# Irrigatron.net
KiCad netlist of a schematic drawn in EasyEDA
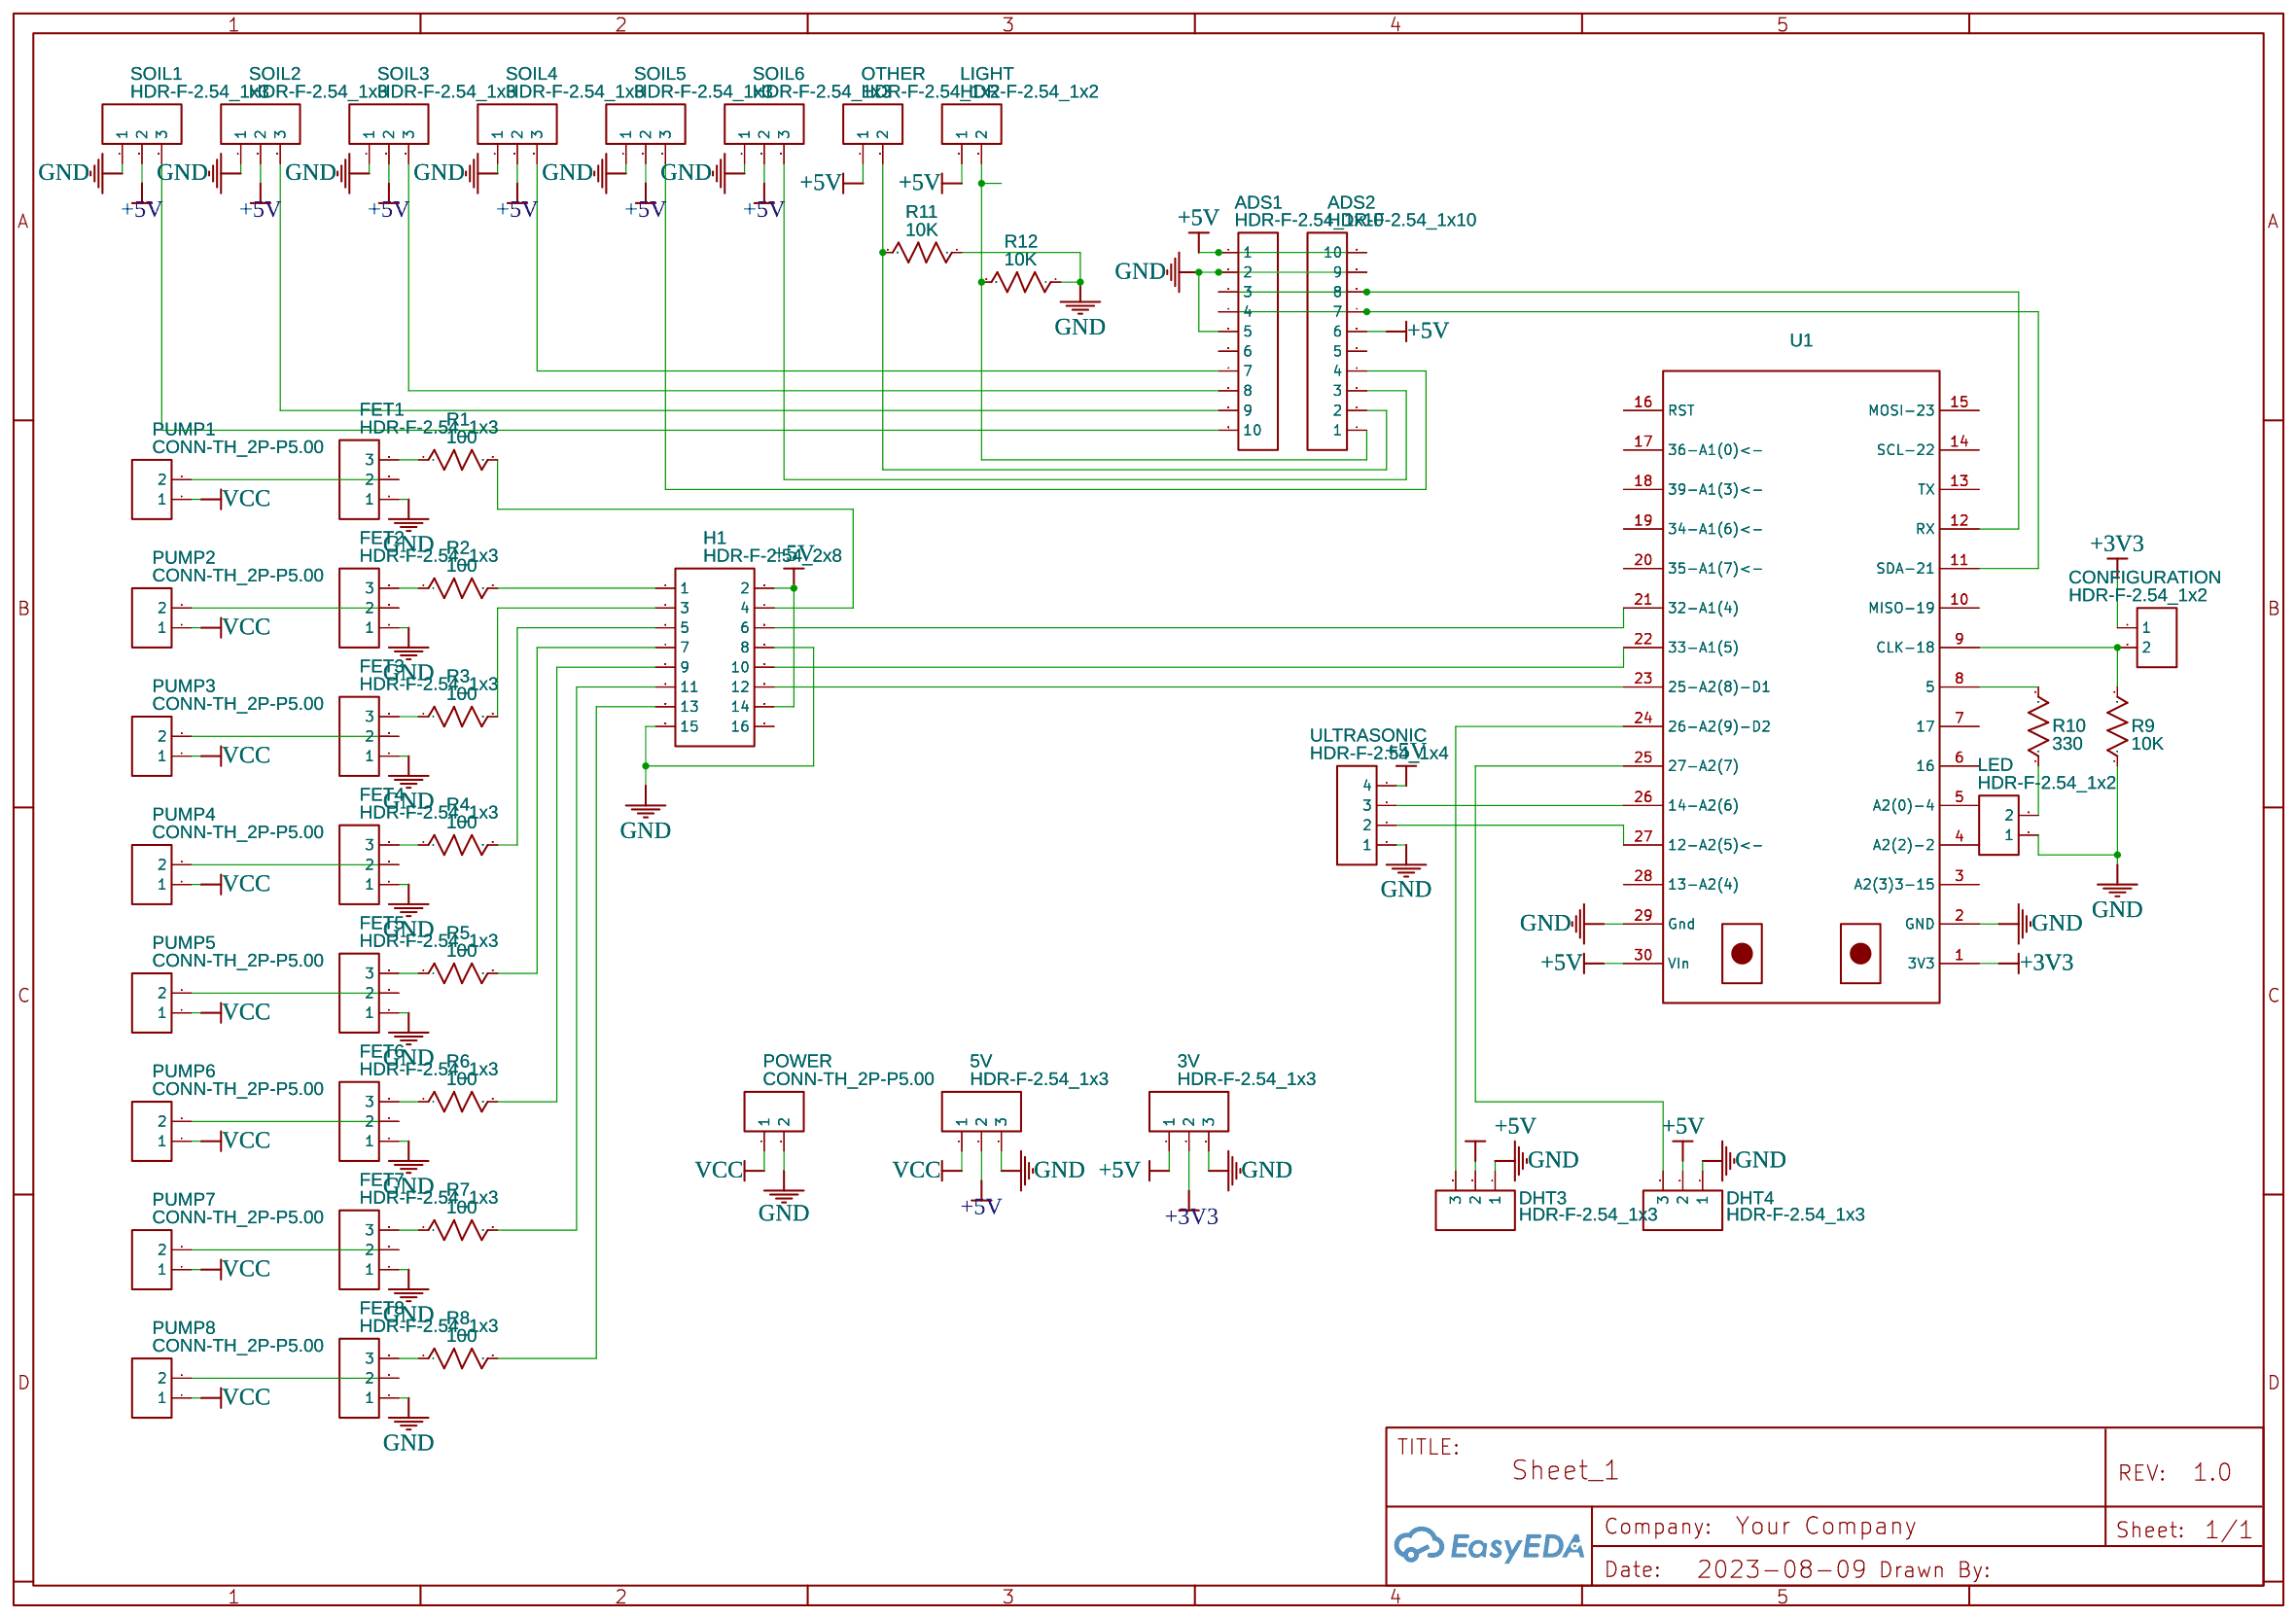
[diagram p0: schematic sheet]

(export (version "E")
  (design (tool "Eeschema 10.0.6"))
  (components
    (comp (ref "3V") (value "HDR-F-2.54_1x3") (libsource (lib "") (part "HDR-F-2.54_1x3_4")))
    (comp (ref "5V") (value "HDR-F-2.54_1x3") (libsource (lib "") (part "HDR-F-2.54_1x3_2")))
    (comp (ref "ADS1") (value "HDR-F-2.54_1x10") (libsource (lib "") (part "HDR-F-2.54_1x10_1")))
    (comp (ref "ADS2") (value "HDR-F-2.54_1x10") (libsource (lib "") (part "HDR-F-2.54_1x10")))
    (comp (ref "CONFIGURATION") (value "HDR-F-2.54_1x2") (libsource (lib "") (part "HDR-F-2.54_1x2_3")))
    (comp (ref "DHT3") (value "HDR-F-2.54_1x3") (libsource (lib "") (part "HDR-F-2.54_1x3_3")))
    (comp (ref "DHT4") (value "HDR-F-2.54_1x3") (libsource (lib "") (part "HDR-F-2.54_1x3_3")))
    (comp (ref "FET1") (value "HDR-F-2.54_1x3") (libsource (lib "") (part "HDR-F-2.54_1x3")))
    (comp (ref "FET2") (value "HDR-F-2.54_1x3") (libsource (lib "") (part "HDR-F-2.54_1x3")))
    (comp (ref "FET3") (value "HDR-F-2.54_1x3") (libsource (lib "") (part "HDR-F-2.54_1x3")))
    (comp (ref "FET4") (value "HDR-F-2.54_1x3") (libsource (lib "") (part "HDR-F-2.54_1x3")))
    (comp (ref "FET5") (value "HDR-F-2.54_1x3") (libsource (lib "") (part "HDR-F-2.54_1x3")))
    (comp (ref "FET6") (value "HDR-F-2.54_1x3") (libsource (lib "") (part "HDR-F-2.54_1x3")))
    (comp (ref "FET7") (value "HDR-F-2.54_1x3") (libsource (lib "") (part "HDR-F-2.54_1x3")))
    (comp (ref "FET8") (value "HDR-F-2.54_1x3") (libsource (lib "") (part "HDR-F-2.54_1x3")))
    (comp (ref "H1") (value "HDR-F-2.54_2x8") (libsource (lib "") (part "HDR-F-2.54_2x8")))
    (comp (ref "LED") (value "HDR-F-2.54_1x2") (libsource (lib "") (part "HDR-F-2.54_1x2")))
    (comp (ref "LIGHT") (value "HDR-F-2.54_1x2") (libsource (lib "") (part "HDR-F-2.54_1x2_2")))
    (comp (ref "OTHER") (value "HDR-F-2.54_1x2") (libsource (lib "") (part "HDR-F-2.54_1x2_1")))
    (comp (ref "POWER") (value "CONN-TH_2P-P5.00") (libsource (lib "") (part "CONN-TH_2P-P5.00")))
    (comp (ref "PUMP1") (value "CONN-TH_2P-P5.00") (libsource (lib "") (part "CONN-TH_2P-P5.00_1")))
    (comp (ref "PUMP2") (value "CONN-TH_2P-P5.00") (libsource (lib "") (part "CONN-TH_2P-P5.00_1")))
    (comp (ref "PUMP3") (value "CONN-TH_2P-P5.00") (libsource (lib "") (part "CONN-TH_2P-P5.00_1")))
    (comp (ref "PUMP4") (value "CONN-TH_2P-P5.00") (libsource (lib "") (part "CONN-TH_2P-P5.00_1")))
    (comp (ref "PUMP5") (value "CONN-TH_2P-P5.00") (libsource (lib "") (part "CONN-TH_2P-P5.00_1")))
    (comp (ref "PUMP6") (value "CONN-TH_2P-P5.00") (libsource (lib "") (part "CONN-TH_2P-P5.00_1")))
    (comp (ref "PUMP7") (value "CONN-TH_2P-P5.00") (libsource (lib "") (part "CONN-TH_2P-P5.00_1")))
    (comp (ref "PUMP8") (value "CONN-TH_2P-P5.00") (libsource (lib "") (part "CONN-TH_2P-P5.00_1")))
    (comp (ref "R1") (value "100") (libsource (lib "") (part "R_0603_US")))
    (comp (ref "R2") (value "100") (libsource (lib "") (part "R_0603_US")))
    (comp (ref "R3") (value "100") (libsource (lib "") (part "R_0603_US")))
    (comp (ref "R4") (value "100") (libsource (lib "") (part "R_0603_US")))
    (comp (ref "R5") (value "100") (libsource (lib "") (part "R_0603_US")))
    (comp (ref "R6") (value "100") (libsource (lib "") (part "R_0603_US")))
    (comp (ref "R7") (value "100") (libsource (lib "") (part "R_0603_US")))
    (comp (ref "R8") (value "100") (libsource (lib "") (part "R_0603_US")))
    (comp (ref "R9") (value "10K") (libsource (lib "") (part "R_0603_US_2")))
    (comp (ref "R10") (value "330") (libsource (lib "") (part "R_0603_US_2")))
    (comp (ref "R11") (value "10K") (libsource (lib "") (part "R_0603_US_1")))
    (comp (ref "R12") (value "10K") (libsource (lib "") (part "R_0603_US_1")))
    (comp (ref "SOIL1") (value "HDR-F-2.54_1x3") (libsource (lib "") (part "HDR-F-2.54_1x3_1")))
    (comp (ref "SOIL2") (value "HDR-F-2.54_1x3") (libsource (lib "") (part "HDR-F-2.54_1x3_1")))
    (comp (ref "SOIL3") (value "HDR-F-2.54_1x3") (libsource (lib "") (part "HDR-F-2.54_1x3_1")))
    (comp (ref "SOIL4") (value "HDR-F-2.54_1x3") (libsource (lib "") (part "HDR-F-2.54_1x3_1")))
    (comp (ref "SOIL5") (value "HDR-F-2.54_1x3") (libsource (lib "") (part "HDR-F-2.54_1x3_1")))
    (comp (ref "SOIL6") (value "HDR-F-2.54_1x3") (libsource (lib "") (part "HDR-F-2.54_1x3_1")))
    (comp (ref "U1") (value "NO") (libsource (lib "") (part "DOIT ESP32 DEVKIT V1 (30pins)")))
    (comp (ref "ULTRASONIC") (value "HDR-F-2.54_1x4") (libsource (lib "") (part "HDR-F-2.54_1x4")))
  )
  (nets
    (net (code "1") (name "+3V3") (class "Default")
      (node (ref "3V") (pin "2") (pinfunction "2_2") (pintype "input"))
      (node (ref "CONFIGURATION") (pin "1") (pinfunction "1_1") (pintype "input"))
      (node (ref "U1") (pin "1") (pinfunction "3V3_1") (pintype "unspecified"))
    )
    (net (code "2") (name "+5V") (class "Default")
      (node (ref "3V") (pin "1") (pinfunction "1_1") (pintype "input"))
      (node (ref "5V") (pin "2") (pinfunction "2_2") (pintype "input"))
      (node (ref "ADS1") (pin "1") (pinfunction "1_1") (pintype "unspecified"))
      (node (ref "ADS2") (pin "10") (pinfunction "10_10") (pintype "unspecified"))
      (node (ref "ADS2") (pin "6") (pinfunction "6_6") (pintype "unspecified"))
      (node (ref "DHT3") (pin "2") (pinfunction "2_2") (pintype "input"))
      (node (ref "DHT4") (pin "2") (pinfunction "2_2") (pintype "input"))
      (node (ref "H1") (pin "14") (pinfunction "14_14") (pintype "input"))
      (node (ref "H1") (pin "2") (pinfunction "2_2") (pintype "input"))
      (node (ref "LIGHT") (pin "1") (pinfunction "1_1") (pintype "input"))
      (node (ref "OTHER") (pin "1") (pinfunction "1_1") (pintype "input"))
      (node (ref "SOIL1") (pin "2") (pinfunction "2_2") (pintype "input"))
      (node (ref "SOIL2") (pin "2") (pinfunction "2_2") (pintype "input"))
      (node (ref "SOIL3") (pin "2") (pinfunction "2_2") (pintype "input"))
      (node (ref "SOIL4") (pin "2") (pinfunction "2_2") (pintype "input"))
      (node (ref "SOIL5") (pin "2") (pinfunction "2_2") (pintype "input"))
      (node (ref "SOIL6") (pin "2") (pinfunction "2_2") (pintype "input"))
      (node (ref "U1") (pin "30") (pinfunction "VIn_30") (pintype "unspecified"))
      (node (ref "ULTRASONIC") (pin "4") (pinfunction "4_4") (pintype "unspecified"))
    )
    (net (code "3") (name "GND") (class "Default")
      (node (ref "3V") (pin "3") (pinfunction "3_3") (pintype "input"))
      (node (ref "5V") (pin "3") (pinfunction "3_3") (pintype "input"))
      (node (ref "ADS1") (pin "2") (pinfunction "2_2") (pintype "unspecified"))
      (node (ref "ADS1") (pin "5") (pinfunction "5_5") (pintype "unspecified"))
      (node (ref "ADS2") (pin "9") (pinfunction "9_9") (pintype "unspecified"))
      (node (ref "DHT3") (pin "1") (pinfunction "1_1") (pintype "input"))
      (node (ref "DHT4") (pin "1") (pinfunction "1_1") (pintype "input"))
      (node (ref "FET1") (pin "1") (pinfunction "1_1") (pintype "input"))
      (node (ref "FET2") (pin "1") (pinfunction "1_1") (pintype "input"))
      (node (ref "FET3") (pin "1") (pinfunction "1_1") (pintype "input"))
      (node (ref "FET4") (pin "1") (pinfunction "1_1") (pintype "input"))
      (node (ref "FET5") (pin "1") (pinfunction "1_1") (pintype "input"))
      (node (ref "FET6") (pin "1") (pinfunction "1_1") (pintype "input"))
      (node (ref "FET7") (pin "1") (pinfunction "1_1") (pintype "input"))
      (node (ref "FET8") (pin "1") (pinfunction "1_1") (pintype "input"))
      (node (ref "H1") (pin "15") (pinfunction "15_15") (pintype "input"))
      (node (ref "H1") (pin "8") (pinfunction "8_8") (pintype "input"))
      (node (ref "LED") (pin "1") (pinfunction "1_1") (pintype "input"))
      (node (ref "POWER") (pin "2") (pinfunction "2_2") (pintype "unspecified"))
      (node (ref "R11") (pin "1") (pinfunction "1_1") (pintype "unspecified"))
      (node (ref "R12") (pin "1") (pinfunction "1_1") (pintype "unspecified"))
      (node (ref "R9") (pin "1") (pinfunction "1_1") (pintype "unspecified"))
      (node (ref "SOIL1") (pin "1") (pinfunction "1_1") (pintype "input"))
      (node (ref "SOIL2") (pin "1") (pinfunction "1_1") (pintype "input"))
      (node (ref "SOIL3") (pin "1") (pinfunction "1_1") (pintype "input"))
      (node (ref "SOIL4") (pin "1") (pinfunction "1_1") (pintype "input"))
      (node (ref "SOIL5") (pin "1") (pinfunction "1_1") (pintype "input"))
      (node (ref "SOIL6") (pin "1") (pinfunction "1_1") (pintype "input"))
      (node (ref "U1") (pin "2") (pinfunction "GND_2") (pintype "unspecified"))
      (node (ref "U1") (pin "29") (pinfunction "Gnd_29") (pintype "unspecified"))
      (node (ref "ULTRASONIC") (pin "1") (pinfunction "1_1") (pintype "unspecified"))
    )
    (net (code "4") (name "Net-(ADS1-Pad7)") (class "Default")
      (node (ref "ADS1") (pin "7") (pinfunction "7_7") (pintype "unspecified"))
      (node (ref "SOIL4") (pin "3") (pinfunction "3_3") (pintype "input"))
    )
    (net (code "5") (name "Net-(ADS1-Pad8)") (class "Default")
      (node (ref "ADS1") (pin "8") (pinfunction "8_8") (pintype "unspecified"))
      (node (ref "SOIL3") (pin "3") (pinfunction "3_3") (pintype "input"))
    )
    (net (code "6") (name "Net-(ADS1-Pad9)") (class "Default")
      (node (ref "ADS1") (pin "9") (pinfunction "9_9") (pintype "unspecified"))
      (node (ref "SOIL2") (pin "3") (pinfunction "3_3") (pintype "input"))
    )
    (net (code "7") (name "Net-(ADS1-Pad10)") (class "Default")
      (node (ref "ADS1") (pin "10") (pinfunction "10_10") (pintype "unspecified"))
      (node (ref "SOIL1") (pin "3") (pinfunction "3_3") (pintype "input"))
    )
    (net (code "8") (name "Net-(ADS2-Pad1)") (class "Default")
      (node (ref "ADS2") (pin "1") (pinfunction "1_1") (pintype "unspecified"))
      (node (ref "LIGHT") (pin "2") (pinfunction "2_2") (pintype "input"))
      (node (ref "R12") (pin "2") (pinfunction "2_2") (pintype "unspecified"))
    )
    (net (code "9") (name "Net-(ADS2-Pad2)") (class "Default")
      (node (ref "ADS2") (pin "2") (pinfunction "2_2") (pintype "unspecified"))
      (node (ref "OTHER") (pin "2") (pinfunction "2_2") (pintype "input"))
      (node (ref "R11") (pin "2") (pinfunction "2_2") (pintype "unspecified"))
    )
    (net (code "10") (name "Net-(ADS2-Pad3)") (class "Default")
      (node (ref "ADS2") (pin "3") (pinfunction "3_3") (pintype "unspecified"))
      (node (ref "SOIL6") (pin "3") (pinfunction "3_3") (pintype "input"))
    )
    (net (code "11") (name "Net-(ADS2-Pad4)") (class "Default")
      (node (ref "ADS2") (pin "4") (pinfunction "4_4") (pintype "unspecified"))
      (node (ref "SOIL5") (pin "3") (pinfunction "3_3") (pintype "input"))
    )
    (net (code "12") (name "Net-(FET1-Pad2)") (class "Default")
      (node (ref "FET1") (pin "2") (pinfunction "2_2") (pintype "input"))
      (node (ref "PUMP1") (pin "2") (pinfunction "2_2") (pintype "unspecified"))
    )
    (net (code "13") (name "Net-(FET1-Pad3)") (class "Default")
      (node (ref "FET1") (pin "3") (pinfunction "3_3") (pintype "input"))
      (node (ref "R1") (pin "1") (pinfunction "1_1") (pintype "unspecified"))
    )
    (net (code "14") (name "Net-(FET2-Pad2)") (class "Default")
      (node (ref "FET2") (pin "2") (pinfunction "2_2") (pintype "input"))
      (node (ref "PUMP2") (pin "2") (pinfunction "2_2") (pintype "unspecified"))
    )
    (net (code "15") (name "Net-(FET2-Pad3)") (class "Default")
      (node (ref "FET2") (pin "3") (pinfunction "3_3") (pintype "input"))
      (node (ref "R2") (pin "1") (pinfunction "1_1") (pintype "unspecified"))
    )
    (net (code "16") (name "Net-(FET3-Pad3)") (class "Default")
      (node (ref "FET3") (pin "3") (pinfunction "3_3") (pintype "input"))
      (node (ref "R3") (pin "1") (pinfunction "1_1") (pintype "unspecified"))
    )
    (net (code "17") (name "Net-(FET4-Pad2)") (class "Default")
      (node (ref "FET4") (pin "2") (pinfunction "2_2") (pintype "input"))
      (node (ref "PUMP4") (pin "2") (pinfunction "2_2") (pintype "unspecified"))
    )
    (net (code "18") (name "Net-(FET4-Pad3)") (class "Default")
      (node (ref "FET4") (pin "3") (pinfunction "3_3") (pintype "input"))
      (node (ref "R4") (pin "1") (pinfunction "1_1") (pintype "unspecified"))
    )
    (net (code "19") (name "Net-(FET5-Pad2)") (class "Default")
      (node (ref "FET5") (pin "2") (pinfunction "2_2") (pintype "input"))
      (node (ref "PUMP5") (pin "2") (pinfunction "2_2") (pintype "unspecified"))
    )
    (net (code "20") (name "Net-(FET5-Pad3)") (class "Default")
      (node (ref "FET5") (pin "3") (pinfunction "3_3") (pintype "input"))
      (node (ref "R5") (pin "1") (pinfunction "1_1") (pintype "unspecified"))
    )
    (net (code "21") (name "Net-(FET6-Pad2)") (class "Default")
      (node (ref "FET6") (pin "2") (pinfunction "2_2") (pintype "input"))
      (node (ref "PUMP6") (pin "2") (pinfunction "2_2") (pintype "unspecified"))
    )
    (net (code "22") (name "Net-(FET6-Pad3)") (class "Default")
      (node (ref "FET6") (pin "3") (pinfunction "3_3") (pintype "input"))
      (node (ref "R6") (pin "1") (pinfunction "1_1") (pintype "unspecified"))
    )
    (net (code "23") (name "Net-(FET7-Pad2)") (class "Default")
      (node (ref "FET7") (pin "2") (pinfunction "2_2") (pintype "input"))
      (node (ref "PUMP7") (pin "2") (pinfunction "2_2") (pintype "unspecified"))
    )
    (net (code "24") (name "Net-(FET7-Pad3)") (class "Default")
      (node (ref "FET7") (pin "3") (pinfunction "3_3") (pintype "input"))
      (node (ref "R7") (pin "1") (pinfunction "1_1") (pintype "unspecified"))
    )
    (net (code "25") (name "Net-(FET8-Pad2)") (class "Default")
      (node (ref "FET8") (pin "2") (pinfunction "2_2") (pintype "input"))
      (node (ref "PUMP8") (pin "2") (pinfunction "2_2") (pintype "unspecified"))
    )
    (net (code "26") (name "Net-(FET8-Pad3)") (class "Default")
      (node (ref "FET8") (pin "3") (pinfunction "3_3") (pintype "input"))
      (node (ref "R8") (pin "1") (pinfunction "1_1") (pintype "unspecified"))
    )
    (net (code "27") (name "Net-(H1-Pad1)") (class "Default")
      (node (ref "H1") (pin "1") (pinfunction "1_1") (pintype "input"))
      (node (ref "R2") (pin "2") (pinfunction "2_2") (pintype "unspecified"))
    )
    (net (code "28") (name "Net-(H1-Pad3)") (class "Default")
      (node (ref "H1") (pin "3") (pinfunction "3_3") (pintype "input"))
      (node (ref "R3") (pin "2") (pinfunction "2_2") (pintype "unspecified"))
    )
    (net (code "29") (name "Net-(H1-Pad4)") (class "Default")
      (node (ref "H1") (pin "4") (pinfunction "4_4") (pintype "input"))
      (node (ref "R1") (pin "2") (pinfunction "2_2") (pintype "unspecified"))
    )
    (net (code "30") (name "Net-(H1-Pad5)") (class "Default")
      (node (ref "H1") (pin "5") (pinfunction "5_5") (pintype "input"))
      (node (ref "R4") (pin "2") (pinfunction "2_2") (pintype "unspecified"))
    )
    (net (code "31") (name "Net-(H1-Pad7)") (class "Default")
      (node (ref "H1") (pin "7") (pinfunction "7_7") (pintype "input"))
      (node (ref "R5") (pin "2") (pinfunction "2_2") (pintype "unspecified"))
    )
    (net (code "32") (name "Net-(H1-Pad9)") (class "Default")
      (node (ref "H1") (pin "9") (pinfunction "9_9") (pintype "input"))
      (node (ref "R6") (pin "2") (pinfunction "2_2") (pintype "unspecified"))
    )
    (net (code "33") (name "Net-(H1-Pad11)") (class "Default")
      (node (ref "H1") (pin "11") (pinfunction "11_11") (pintype "input"))
      (node (ref "R7") (pin "2") (pinfunction "2_2") (pintype "unspecified"))
    )
    (net (code "34") (name "Net-(H1-Pad13)") (class "Default")
      (node (ref "H1") (pin "13") (pinfunction "13_13") (pintype "input"))
      (node (ref "R8") (pin "2") (pinfunction "2_2") (pintype "unspecified"))
    )
    (net (code "35") (name "Net-(LED-Pad2)") (class "Default")
      (node (ref "LED") (pin "2") (pinfunction "2_2") (pintype "input"))
      (node (ref "R10") (pin "1") (pinfunction "1_1") (pintype "unspecified"))
    )
    (net (code "36") (name "Net-(U1-5)") (class "Default")
      (node (ref "R10") (pin "2") (pinfunction "2_2") (pintype "unspecified"))
      (node (ref "U1") (pin "8") (pinfunction "5_8") (pintype "unspecified"))
    )
    (net (code "37") (name "Net-(U1-12-A2(5)<-)") (class "Default")
      (node (ref "U1") (pin "27") (pinfunction "12-A2(5)<-_27") (pintype "unspecified"))
      (node (ref "ULTRASONIC") (pin "2") (pinfunction "2_2") (pintype "unspecified"))
    )
    (net (code "38") (name "Net-(U1-14-A2(6))") (class "Default")
      (node (ref "U1") (pin "26") (pinfunction "14-A2(6)_26") (pintype "unspecified"))
      (node (ref "ULTRASONIC") (pin "3") (pinfunction "3_3") (pintype "unspecified"))
    )
    (net (code "39") (name "Net-(U1-25-A2(8)-D1)") (class "Default")
      (node (ref "H1") (pin "12") (pinfunction "12_12") (pintype "input"))
      (node (ref "U1") (pin "23") (pinfunction "25-A2(8)-D1_23") (pintype "unspecified"))
    )
    (net (code "40") (name "Net-(U1-26-A2(9)-D2)") (class "Default")
      (node (ref "DHT3") (pin "3") (pinfunction "3_3") (pintype "input"))
      (node (ref "U1") (pin "24") (pinfunction "26-A2(9)-D2_24") (pintype "unspecified"))
    )
    (net (code "41") (name "Net-(U1-27-A2(7))") (class "Default")
      (node (ref "DHT4") (pin "3") (pinfunction "3_3") (pintype "input"))
      (node (ref "U1") (pin "25") (pinfunction "27-A2(7)_25") (pintype "unspecified"))
    )
    (net (code "42") (name "Net-(U1-32-A1(4))") (class "Default")
      (node (ref "H1") (pin "6") (pinfunction "6_6") (pintype "input"))
      (node (ref "U1") (pin "21") (pinfunction "32-A1(4)_21") (pintype "unspecified"))
    )
    (net (code "43") (name "Net-(U1-33-A1(5))") (class "Default")
      (node (ref "H1") (pin "10") (pinfunction "10_10") (pintype "input"))
      (node (ref "U1") (pin "22") (pinfunction "33-A1(5)_22") (pintype "unspecified"))
    )
    (net (code "44") (name "Net-(U1-CLK-18)") (class "Default")
      (node (ref "CONFIGURATION") (pin "2") (pinfunction "2_2") (pintype "input"))
      (node (ref "R9") (pin "2") (pinfunction "2_2") (pintype "unspecified"))
      (node (ref "U1") (pin "9") (pinfunction "CLK-18_9") (pintype "unspecified"))
    )
    (net (code "45") (name "Net-(U1-RX)") (class "Default")
      (node (ref "ADS1") (pin "3") (pinfunction "3_3") (pintype "unspecified"))
      (node (ref "ADS2") (pin "8") (pinfunction "8_8") (pintype "unspecified"))
      (node (ref "U1") (pin "12") (pinfunction "RX_12") (pintype "unspecified"))
    )
    (net (code "46") (name "Net-(U1-SDA-21)") (class "Default")
      (node (ref "ADS1") (pin "4") (pinfunction "4_4") (pintype "unspecified"))
      (node (ref "ADS2") (pin "7") (pinfunction "7_7") (pintype "unspecified"))
      (node (ref "U1") (pin "11") (pinfunction "SDA-21_11") (pintype "unspecified"))
    )
    (net (code "47") (name "VCC") (class "Default")
      (node (ref "5V") (pin "1") (pinfunction "1_1") (pintype "input"))
      (node (ref "POWER") (pin "1") (pinfunction "1_1") (pintype "unspecified"))
      (node (ref "PUMP1") (pin "1") (pinfunction "1_1") (pintype "unspecified"))
      (node (ref "PUMP2") (pin "1") (pinfunction "1_1") (pintype "unspecified"))
      (node (ref "PUMP3") (pin "1") (pinfunction "1_1") (pintype "unspecified"))
      (node (ref "PUMP4") (pin "1") (pinfunction "1_1") (pintype "unspecified"))
      (node (ref "PUMP5") (pin "1") (pinfunction "1_1") (pintype "unspecified"))
      (node (ref "PUMP6") (pin "1") (pinfunction "1_1") (pintype "unspecified"))
      (node (ref "PUMP7") (pin "1") (pinfunction "1_1") (pintype "unspecified"))
      (node (ref "PUMP8") (pin "1") (pinfunction "1_1") (pintype "unspecified"))
    )
    (net (code "48") (name "unconnected-(ADS1-Pad6)") (class "Default")
      (node (ref "ADS1") (pin "6") (pinfunction "6_6") (pintype "unspecified"))
    )
    (net (code "49") (name "unconnected-(ADS2-Pad5)") (class "Default")
      (node (ref "ADS2") (pin "5") (pinfunction "5_5") (pintype "unspecified"))
    )
    (net (code "50") (name "unconnected-(FET3-Pad2)") (class "Default")
      (node (ref "FET3") (pin "2") (pinfunction "2_2") (pintype "input"))
    )
    (net (code "51") (name "unconnected-(H1-Pad16)") (class "Default")
      (node (ref "H1") (pin "16") (pinfunction "16_16") (pintype "input"))
    )
    (net (code "52") (name "unconnected-(PUMP3-Pad2)") (class "Default")
      (node (ref "PUMP3") (pin "2") (pinfunction "2_2") (pintype "unspecified"))
    )
    (net (code "53") (name "unconnected-(U1-13-A2(4)-Pad28)") (class "Default")
      (node (ref "U1") (pin "28") (pinfunction "13-A2(4)_28") (pintype "unspecified"))
    )
    (net (code "54") (name "unconnected-(U1-16-Pad6)") (class "Default")
      (node (ref "U1") (pin "6") (pinfunction "16_6") (pintype "unspecified"))
    )
    (net (code "55") (name "unconnected-(U1-17-Pad7)") (class "Default")
      (node (ref "U1") (pin "7") (pinfunction "17_7") (pintype "unspecified"))
    )
    (net (code "56") (name "unconnected-(U1-34-A1(6)<--Pad19)") (class "Default")
      (node (ref "U1") (pin "19") (pinfunction "34-A1(6)<-_19") (pintype "unspecified"))
    )
    (net (code "57") (name "unconnected-(U1-35-A1(7)<--Pad20)") (class "Default")
      (node (ref "U1") (pin "20") (pinfunction "35-A1(7)<-_20") (pintype "unspecified"))
    )
    (net (code "58") (name "unconnected-(U1-36-A1(0)<--Pad17)") (class "Default")
      (node (ref "U1") (pin "17") (pinfunction "36-A1(0)<-_17") (pintype "unspecified"))
    )
    (net (code "59") (name "unconnected-(U1-39-A1(3)<--Pad18)") (class "Default")
      (node (ref "U1") (pin "18") (pinfunction "39-A1(3)<-_18") (pintype "unspecified"))
    )
    (net (code "60") (name "unconnected-(U1-A2(0)-4-Pad5)") (class "Default")
      (node (ref "U1") (pin "5") (pinfunction "A2(0)-4_5") (pintype "unspecified"))
    )
    (net (code "61") (name "unconnected-(U1-A2(2)-2-Pad4)") (class "Default")
      (node (ref "U1") (pin "4") (pinfunction "A2(2)-2_4") (pintype "unspecified"))
    )
    (net (code "62") (name "unconnected-(U1-A2(3)3-15-Pad3)") (class "Default")
      (node (ref "U1") (pin "3") (pinfunction "A2(3)3-15_3") (pintype "unspecified"))
    )
    (net (code "63") (name "unconnected-(U1-MISO-19-Pad10)") (class "Default")
      (node (ref "U1") (pin "10") (pinfunction "MISO-19_10") (pintype "unspecified"))
    )
    (net (code "64") (name "unconnected-(U1-MOSI-23-Pad15)") (class "Default")
      (node (ref "U1") (pin "15") (pinfunction "MOSI-23_15") (pintype "unspecified"))
    )
    (net (code "65") (name "unconnected-(U1-RST-Pad16)") (class "Default")
      (node (ref "U1") (pin "16") (pinfunction "RST_16") (pintype "unspecified"))
    )
    (net (code "66") (name "unconnected-(U1-SCL-22-Pad14)") (class "Default")
      (node (ref "U1") (pin "14") (pinfunction "SCL-22_14") (pintype "unspecified"))
    )
    (net (code "67") (name "unconnected-(U1-TX-Pad13)") (class "Default")
      (node (ref "U1") (pin "13") (pinfunction "TX_13") (pintype "unspecified"))
    )
  )
)
